# 11-Flow_meter.net
KiCad netlist of a schematic drawn in Altium Designer
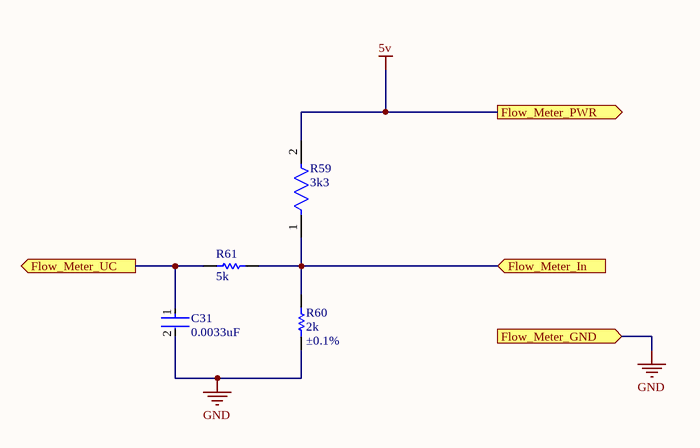
[diagram p0: 11-Flow meter.SchDoc]

(export (version "E")
  (design (tool "Eeschema 10.0.6"))
  (components
    (comp (ref "C31")
      (value "0.0033uF")
      (footprint "FP-GRM188-0_1-e0_2_0_5-IPC_A")
      (description "Chip Multilayer Ceramic Capacitors for General Purpose, 0603, 3300pF, C0G, 30ppm/°C, 5%, 50V")
      (fields (field (name "TOLERANCE") "5%") (field (name "VOLTAGE") "50V"))
      (libsource (lib "Altium Content Vault") (part "11868f565c42a9108669ba33697ecf6"))
    )
    (comp (ref "R59")
      (value "3k3")
      (footprint "FP-RC0603-0_55-MFG")
      (fields (field (name "TOLERANCE") "1%"))
      (libsource (lib "Altium Content Vault") (part "1029c3af85768c4190bb7ad29bc67b5"))
    )
    (comp (ref "R60")
      (value "2k")
      (footprint "1608[0603]")
      (description "Resistor")
      (fields
        (field (name "MANUFACTURER") "Yageo")
        (field (name "MANUFACTURER PART NUMBER") "AT0603BRD072KL")
        (field (name "TOLERANCE") "±0.1%")
      )
      (libsource (lib "Miscellaneous Devices") (part "Res1"))
    )
    (comp (ref "R61")
      (value "5k")
      (footprint "1608[0603]")
      (description "Resistor")
      (fields
        (field (name "MANUFACTURER") "Yageo")
        (field (name "MANUFACTURER PART NUMBER") "AT0603BRD072KL")
      )
      (libsource (lib "Miscellaneous Devices") (part "Res1"))
    )
  )
  (nets
    (net (code "1") (name "/Flow_Meter_In") (class "Default")
      (node (ref "R59") (pin "1") (pinfunction "1_1") (pintype "passive"))
      (node (ref "R60") (pin "2") (pinfunction "2_2") (pintype "passive"))
      (node (ref "R61") (pin "1") (pinfunction "1_1") (pintype "passive"))
    )
    (net (code "2") (name "/Flow_Meter_UC") (class "Default")
      (node (ref "C31") (pin "1") (pinfunction "1_1") (pintype "passive"))
      (node (ref "R61") (pin "2") (pinfunction "2_2") (pintype "passive"))
    )
    (net (code "3") (name "5v") (class "Default")
      (node (ref "R59") (pin "2") (pinfunction "2_2") (pintype "passive"))
    )
    (net (code "4") (name "GND") (class "Default")
      (node (ref "C31") (pin "2") (pinfunction "2_2") (pintype "passive"))
      (node (ref "R60") (pin "1") (pinfunction "1_1") (pintype "passive"))
    )
  )
)
